# Peripherals.net
KiCad netlist of a schematic drawn in Altium Designer
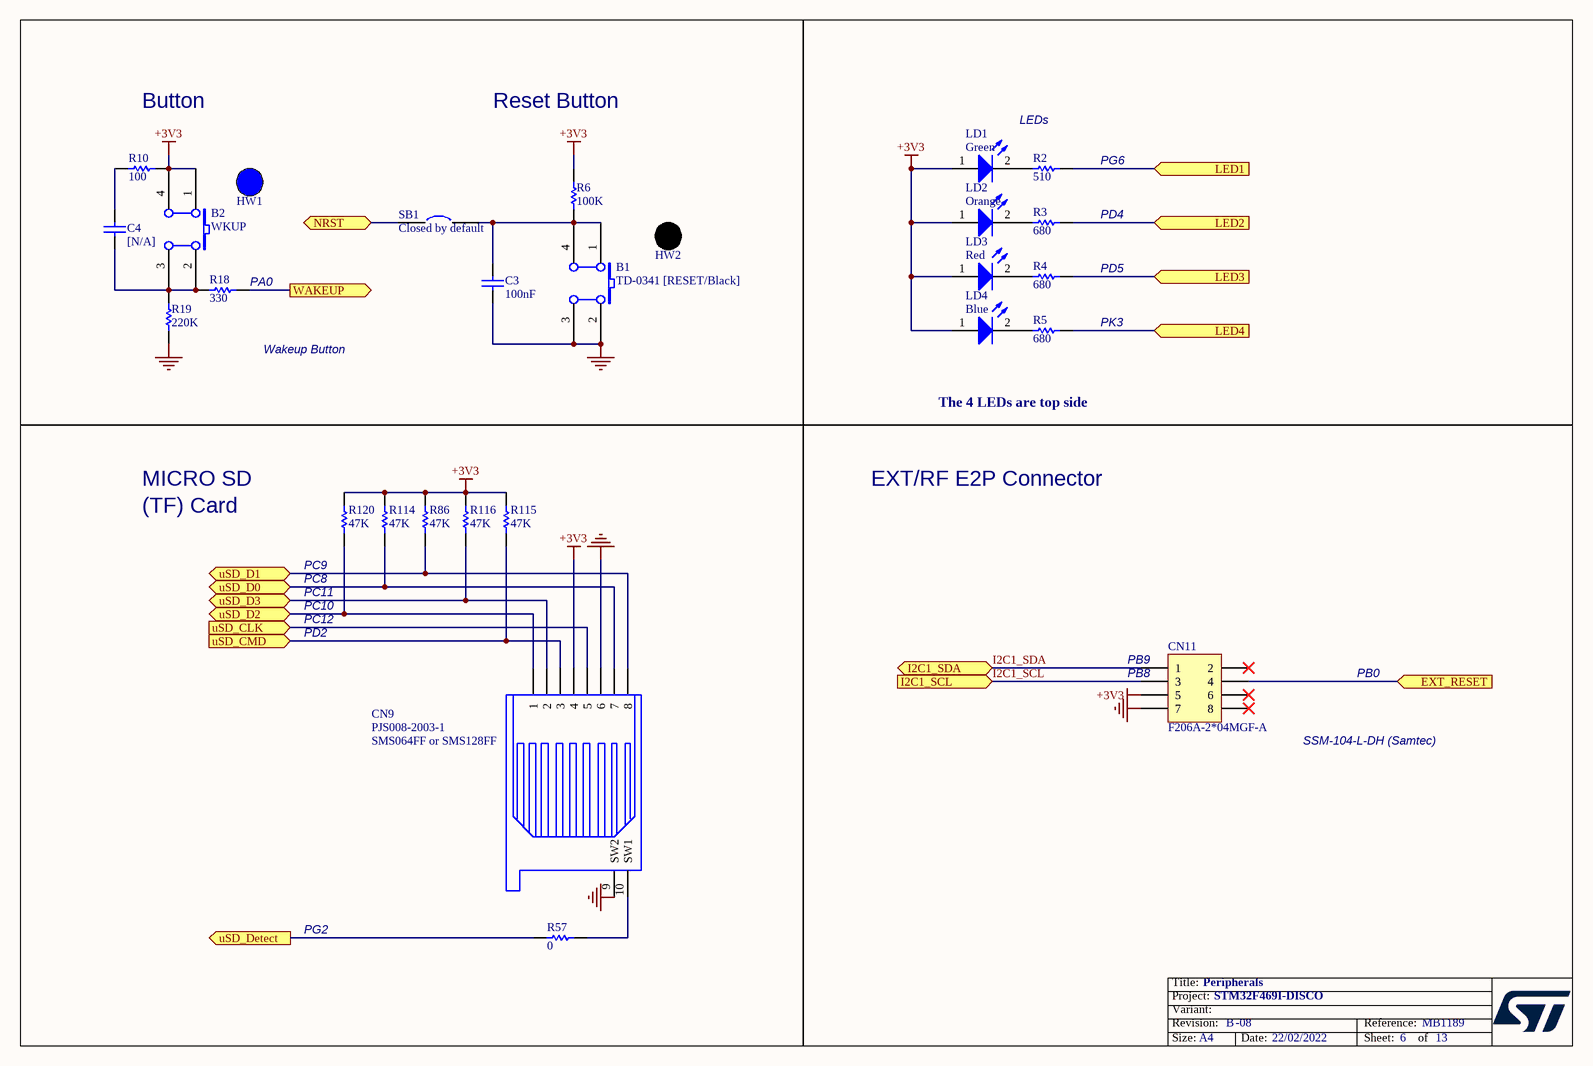
[diagram p0: Peripherals.SchDoc]

(export (version "E")
  (design (tool "Eeschema 10.0.6"))
  (components
    (comp (ref "B1")
      (value "TD-0341 [RESET/Black]")
      (footprint "PB10")
      (description "SE PUSHBUTTON")
      (libsource (lib "Documents") (part "SW PUSHBUTTON"))
    )
    (comp (ref "B2")
      (value "WKUP")
      (footprint "PB10")
      (description "SE PUSHBUTTON")
      (libsource (lib "Documents") (part "SW PUSHBUTTON"))
    )
    (comp (ref "C3")
      (value "100nF")
      (footprint "0402C")
      (description "Capacitor")
      (fields (field (name "PUBLISHER") "Altium Limited"))
      (libsource (lib "Miscellaneous Devices") (part "CAP"))
    )
    (comp (ref "C4")
      (value "[N/A]")
      (footprint "0603C")
      (description "Capacitor")
      (fields (field (name "PUBLISHER") "Altium Limited"))
      (libsource (lib "Miscellaneous Devices") (part "CAP"))
    )
    (comp (ref "CN9")
      (value "PJS008-2003-1")
      (footprint "MSD_PJS008_")
      (libsource (lib "MB525") (part "SMS016AFA5E"))
    )
    (comp (ref "CN11")
      (value "F206A-2*04MGF-A")
      (footprint "SSM-104-L-DH")
      (description "Header, 4-Pin, Dual row")
      (fields (field (name "PUBLISHER") "Altium Limited"))
      (libsource (lib "mb1045") (part "SSM-104-L-DH"))
    )
    (comp (ref "HW1")
      (value "BUTTON_HAT_BLUE")
      (description "switch hat,blue")
      (libsource (lib "MB1189") (part "BUTTON_HAT_BLUE"))
    )
    (comp (ref "HW2")
      (value "BUTTON_HAT_BLACK")
      (description "switch hat,black")
      (libsource (lib "MB1189") (part "BUTTON_HAT_BLACK"))
    )
    (comp (ref "LD1")
      (value "Green")
      (footprint "0603D")
      (description "Typical RED, GREEN, YELLOW, AMBER GaAs LED")
      (fields (field (name "PUBLISHER") "Altium Limited"))
      (libsource (lib "Miscellaneous Devices") (part "LED2"))
    )
    (comp (ref "LD2")
      (value "Orange")
      (footprint "0603D")
      (description "Typical RED, GREEN, YELLOW, AMBER GaAs LED")
      (fields (field (name "PUBLISHER") "Altium Limited"))
      (libsource (lib "Miscellaneous Devices") (part "LED2"))
    )
    (comp (ref "LD3")
      (value "Red")
      (footprint "0603D")
      (description "Typical RED, GREEN, YELLOW, AMBER GaAs LED")
      (fields (field (name "PUBLISHER") "Altium Limited"))
      (libsource (lib "Miscellaneous Devices") (part "LED2"))
    )
    (comp (ref "LD4")
      (value "Blue")
      (footprint "0603D")
      (description "Typical RED, GREEN, YELLOW, AMBER GaAs LED")
      (fields (field (name "PUBLISHER") "Altium Limited"))
      (libsource (lib "Miscellaneous Devices") (part "LED2"))
    )
    (comp (ref "R2")
      (value "510")
      (footprint "0603R")
      (description "Resistor")
      (fields (field (name "PUBLISHER") "Altium Limited"))
      (libsource (lib "Miscellaneous Devices") (part "Res1"))
    )
    (comp (ref "R3")
      (value "680")
      (footprint "0603R")
      (description "Resistor")
      (fields (field (name "PUBLISHER") "Altium Limited"))
      (libsource (lib "Miscellaneous Devices") (part "Res1"))
    )
    (comp (ref "R4")
      (value "680")
      (footprint "0603R")
      (description "Resistor")
      (fields (field (name "PUBLISHER") "Altium Limited"))
      (libsource (lib "Miscellaneous Devices") (part "Res1"))
    )
    (comp (ref "R5")
      (value "680")
      (footprint "0603R")
      (description "Resistor")
      (fields (field (name "PUBLISHER") "Altium Limited"))
      (libsource (lib "Miscellaneous Devices") (part "Res1"))
    )
    (comp (ref "R6")
      (value "100K")
      (footprint "0603R")
      (description "Resistor")
      (fields (field (name "PUBLISHER") "Altium Limited"))
      (libsource (lib "Miscellaneous Devices") (part "res1"))
    )
    (comp (ref "R10")
      (value "100")
      (footprint "0603R")
      (description "Resistor")
      (fields (field (name "PUBLISHER") "Altium Limited"))
      (libsource (lib "Miscellaneous Devices") (part "Res1"))
    )
    (comp (ref "R18")
      (value "330")
      (footprint "0603R")
      (description "Resistor")
      (fields (field (name "PUBLISHER") "Altium Limited"))
      (libsource (lib "Miscellaneous Devices") (part "Res1"))
    )
    (comp (ref "R19")
      (value "220K")
      (footprint "0603R")
      (description "Resistor")
      (fields (field (name "PUBLISHER") "Altium Limited"))
      (libsource (lib "Miscellaneous Devices") (part "res1"))
    )
    (comp (ref "R57")
      (value "0")
      (footprint "0603R")
      (description "Resistor")
      (fields (field (name "PUBLISHER") "Altium Limited"))
      (libsource (lib "Miscellaneous Devices") (part "Res1"))
    )
    (comp (ref "R86")
      (value "47K")
      (footprint "0603R")
      (description "Resistor")
      (fields (field (name "PUBLISHER") "Altium Limited"))
      (libsource (lib "Miscellaneous Devices") (part "res1"))
    )
    (comp (ref "R114")
      (value "47K")
      (footprint "0603R")
      (description "Resistor")
      (fields (field (name "PUBLISHER") "Altium Limited"))
      (libsource (lib "Miscellaneous Devices") (part "res1"))
    )
    (comp (ref "R115")
      (value "47K")
      (footprint "0603R")
      (description "Resistor")
      (fields (field (name "PUBLISHER") "Altium Limited"))
      (libsource (lib "Miscellaneous Devices") (part "res1"))
    )
    (comp (ref "R116")
      (value "47K")
      (footprint "0603R")
      (description "Resistor")
      (fields (field (name "PUBLISHER") "Altium Limited"))
      (libsource (lib "Miscellaneous Devices") (part "res1"))
    )
    (comp (ref "R120")
      (value "47K")
      (footprint "0603R")
      (description "Resistor")
      (fields (field (name "PUBLISHER") "Altium Limited"))
      (libsource (lib "Miscellaneous Devices") (part "res1"))
    )
    (comp (ref "SB1")
      (value "Closed by default")
      (footprint "SB_0603")
      (description "Circuit Breaker")
      (fields (field (name "PUBLISHER") "Altium Limited"))
      (libsource (lib "Miscellaneous Devices") (part "Circuit Breaker"))
    )
  )
  (nets
    (net (code "1") (name "+3V3") (class "Default")
      (node (ref "B2") (pin "1") (pinfunction "A0_1") (pintype "passive"))
      (node (ref "B2") (pin "4") (pinfunction "A1_4") (pintype "passive"))
      (node (ref "CN11") (pin "5") (pinfunction "5_5") (pintype "passive"))
      (node (ref "CN9") (pin "4") (pinfunction "4_4") (pintype "passive"))
      (node (ref "LD1") (pin "1") (pinfunction "A_1") (pintype "passive"))
      (node (ref "LD2") (pin "1") (pinfunction "A_1") (pintype "passive"))
      (node (ref "LD3") (pin "1") (pinfunction "A_1") (pintype "passive"))
      (node (ref "LD4") (pin "1") (pinfunction "A_1") (pintype "passive"))
      (node (ref "R10") (pin "1") (pinfunction "1_1") (pintype "passive"))
      (node (ref "R114") (pin "1") (pinfunction "1_1") (pintype "passive"))
      (node (ref "R115") (pin "1") (pinfunction "1_1") (pintype "passive"))
      (node (ref "R116") (pin "1") (pinfunction "1_1") (pintype "passive"))
      (node (ref "R120") (pin "1") (pinfunction "1_1") (pintype "passive"))
      (node (ref "R6") (pin "1") (pinfunction "1_1") (pintype "passive"))
      (node (ref "R86") (pin "1") (pinfunction "1_1") (pintype "passive"))
    )
    (net (code "2") (name "/EXT_RESET") (class "Default")
      (node (ref "CN11") (pin "4") (pinfunction "4_4") (pintype "passive"))
    )
    (net (code "3") (name "/I2C1_SCL") (class "Default")
      (node (ref "CN11") (pin "3") (pinfunction "3_3") (pintype "passive"))
    )
    (net (code "4") (name "/I2C1_SDA") (class "Default")
      (node (ref "CN11") (pin "1") (pinfunction "1_1") (pintype "passive"))
    )
    (net (code "5") (name "/LED1") (class "Default")
      (node (ref "R2") (pin "1") (pinfunction "1_1") (pintype "passive"))
    )
    (net (code "6") (name "/LED2") (class "Default")
      (node (ref "R3") (pin "1") (pinfunction "1_1") (pintype "passive"))
    )
    (net (code "7") (name "/LED3") (class "Default")
      (node (ref "R4") (pin "1") (pinfunction "1_1") (pintype "passive"))
    )
    (net (code "8") (name "/LED4") (class "Default")
      (node (ref "R5") (pin "1") (pinfunction "1_1") (pintype "passive"))
    )
    (net (code "9") (name "/NRST") (class "Default")
      (node (ref "SB1") (pin "1") (pinfunction "1_1") (pintype "passive"))
    )
    (net (code "10") (name "/WAKEUP") (class "Default")
      (node (ref "R18") (pin "2") (pinfunction "2_2") (pintype "passive"))
    )
    (net (code "11") (name "/uSD_CLK") (class "Default")
      (node (ref "CN9") (pin "5") (pinfunction "5_5") (pintype "passive"))
    )
    (net (code "12") (name "/uSD_CMD") (class "Default")
      (node (ref "CN9") (pin "3") (pinfunction "3_3") (pintype "passive"))
      (node (ref "R115") (pin "2") (pinfunction "2_2") (pintype "passive"))
    )
    (net (code "13") (name "/uSD_D0") (class "Default")
      (node (ref "CN9") (pin "7") (pinfunction "7_7") (pintype "passive"))
      (node (ref "R114") (pin "2") (pinfunction "2_2") (pintype "passive"))
    )
    (net (code "14") (name "/uSD_D1") (class "Default")
      (node (ref "CN9") (pin "8") (pinfunction "8_8") (pintype "passive"))
      (node (ref "R86") (pin "2") (pinfunction "2_2") (pintype "passive"))
    )
    (net (code "15") (name "/uSD_D2") (class "Default")
      (node (ref "CN9") (pin "1") (pinfunction "1_1") (pintype "passive"))
      (node (ref "R120") (pin "2") (pinfunction "2_2") (pintype "passive"))
    )
    (net (code "16") (name "/uSD_D3") (class "Default")
      (node (ref "CN9") (pin "2") (pinfunction "2_2") (pintype "passive"))
      (node (ref "R116") (pin "2") (pinfunction "2_2") (pintype "passive"))
    )
    (net (code "17") (name "/uSD_Detect") (class "Default")
      (node (ref "R57") (pin "1") (pinfunction "1_1") (pintype "passive"))
    )
    (net (code "18") (name "GND") (class "Default")
      (node (ref "B1") (pin "2") (pinfunction "B0_2") (pintype "passive"))
      (node (ref "B1") (pin "3") (pinfunction "B1_3") (pintype "passive"))
      (node (ref "C3") (pin "1") (pinfunction "1_1") (pintype "passive"))
      (node (ref "CN11") (pin "7") (pinfunction "7_7") (pintype "passive"))
      (node (ref "CN9") (pin "6") (pinfunction "6_6") (pintype "passive"))
      (node (ref "CN9") (pin "9") (pinfunction "SW2_9") (pintype "passive"))
      (node (ref "R19") (pin "2") (pinfunction "2_2") (pintype "passive"))
    )
    (net (code "19") (name "Net-(B1-A0)") (class "Default")
      (node (ref "B1") (pin "1") (pinfunction "A0_1") (pintype "passive"))
      (node (ref "B1") (pin "4") (pinfunction "A1_4") (pintype "passive"))
      (node (ref "C3") (pin "2") (pinfunction "2_2") (pintype "passive"))
      (node (ref "R6") (pin "2") (pinfunction "2_2") (pintype "passive"))
      (node (ref "SB1") (pin "2") (pinfunction "2_2") (pintype "passive"))
    )
    (net (code "20") (name "Net-(B2-B0)") (class "Default")
      (node (ref "B2") (pin "2") (pinfunction "B0_2") (pintype "passive"))
      (node (ref "B2") (pin "3") (pinfunction "B1_3") (pintype "passive"))
      (node (ref "C4") (pin "2") (pinfunction "2_2") (pintype "passive"))
      (node (ref "R18") (pin "1") (pinfunction "1_1") (pintype "passive"))
      (node (ref "R19") (pin "1") (pinfunction "1_1") (pintype "passive"))
    )
    (net (code "21") (name "Net-(C4-Pad1)") (class "Default")
      (node (ref "C4") (pin "1") (pinfunction "1_1") (pintype "passive"))
      (node (ref "R10") (pin "2") (pinfunction "2_2") (pintype "passive"))
    )
    (net (code "22") (name "Net-(CN9-SW1)") (class "Default")
      (node (ref "CN9") (pin "10") (pinfunction "SW1_10") (pintype "passive"))
      (node (ref "R57") (pin "2") (pinfunction "2_2") (pintype "passive"))
    )
    (net (code "23") (name "Net-(LD1-K)") (class "Default")
      (node (ref "LD1") (pin "2") (pinfunction "K_2") (pintype "passive"))
      (node (ref "R2") (pin "2") (pinfunction "2_2") (pintype "passive"))
    )
    (net (code "24") (name "Net-(LD2-K)") (class "Default")
      (node (ref "LD2") (pin "2") (pinfunction "K_2") (pintype "passive"))
      (node (ref "R3") (pin "2") (pinfunction "2_2") (pintype "passive"))
    )
    (net (code "25") (name "Net-(LD3-K)") (class "Default")
      (node (ref "LD3") (pin "2") (pinfunction "K_2") (pintype "passive"))
      (node (ref "R4") (pin "2") (pinfunction "2_2") (pintype "passive"))
    )
    (net (code "26") (name "Net-(LD4-K)") (class "Default")
      (node (ref "LD4") (pin "2") (pinfunction "K_2") (pintype "passive"))
      (node (ref "R5") (pin "2") (pinfunction "2_2") (pintype "passive"))
    )
    (net (code "27") (name "unconnected-(CN11-Pad2)") (class "Default")
      (node (ref "CN11") (pin "2") (pinfunction "2_2") (pintype "passive+no_connect"))
    )
    (net (code "28") (name "unconnected-(CN11-Pad6)") (class "Default")
      (node (ref "CN11") (pin "6") (pinfunction "6_6") (pintype "passive+no_connect"))
    )
    (net (code "29") (name "unconnected-(CN11-Pad8)") (class "Default")
      (node (ref "CN11") (pin "8") (pinfunction "8_8") (pintype "passive+no_connect"))
    )
  )
)
